# Sheet1.net
KiCad netlist of a schematic drawn in Altium Designer
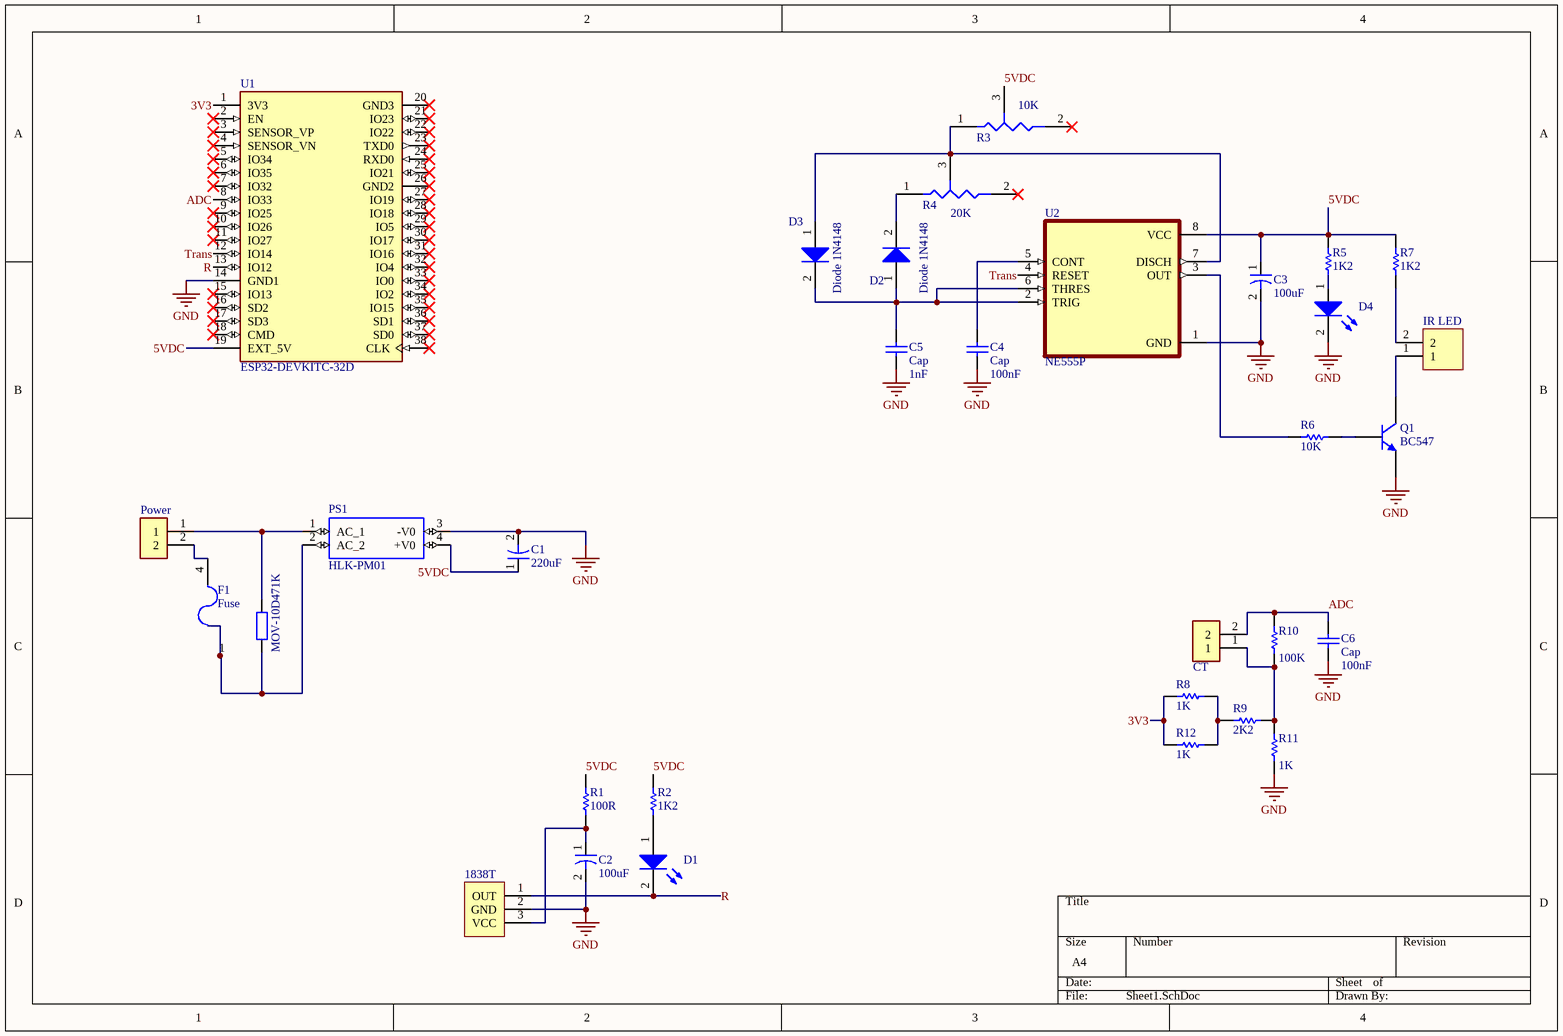
[diagram p0: Sheet1.SchDoc]

(export (version "E")
  (design (tool "Eeschema 10.0.6"))
  (components
    (comp (ref "1838T")
      (value "Header 3")
      (footprint "TSOP 1838T")
      (description "Header, 3-Pin")
      (fields (field (name "PUBLISHER") "Altium Limited"))
      (libsource (lib "Miscellaneous Connectors") (part "Header 3"))
    )
    (comp (ref "C1")
      (value "220uF")
      (footprint "CAPR5-4X5")
      (description "Capacitor")
      (fields (field (name "Comment") "Cap2") (field (name "PUBLISHER") "Altium Limited"))
      (libsource (lib "Miscellaneous Devices") (part "Cap2"))
    )
    (comp (ref "C2")
      (value "100uF")
      (footprint "CAPR5-4X5")
      (description "Capacitor")
      (fields (field (name "Comment") "Cap2") (field (name "PUBLISHER") "Altium Limited"))
      (libsource (lib "Miscellaneous Devices") (part "Cap2"))
    )
    (comp (ref "C3")
      (value "100uF")
      (footprint "CAPR5-4X5")
      (description "Capacitor")
      (fields (field (name "Comment") "Cap2") (field (name "PUBLISHER") "Altium Limited"))
      (libsource (lib "Miscellaneous Devices") (part "Cap2"))
    )
    (comp (ref "C4")
      (value "Cap")
      (footprint "RAD-0.3")
      (description "Capacitor")
      (fields (field (name "ALTIUM_VALUE") "100nF") (field (name "PUBLISHER") "Altium Limited"))
      (libsource (lib "Miscellaneous Devices") (part "Cap"))
    )
    (comp (ref "C5")
      (value "Cap")
      (footprint "RAD-0.3")
      (description "Capacitor")
      (fields (field (name "ALTIUM_VALUE") "1nF") (field (name "PUBLISHER") "Altium Limited"))
      (libsource (lib "Miscellaneous Devices") (part "Cap"))
    )
    (comp (ref "C6")
      (value "Cap")
      (footprint "RAD-0.3")
      (description "Capacitor")
      (fields (field (name "ALTIUM_VALUE") "100nF") (field (name "PUBLISHER") "Altium Limited"))
      (libsource (lib "Miscellaneous Devices") (part "Cap"))
    )
    (comp (ref "CT")
      (value "282837-2")
      (footprint "TE_282837-2")
      (description "Connector Terminal Blocks Receptacle 2 Position 5.08mm Solder Straight Thru-Hole 13.5A/Contact")
      (fields (field (name "MF") "TE Connectivity") (field (name "DIGI-KEY_PART_NUMBER") "A113320-ND"))
      (libsource (lib "282837-2") (part "282837-2"))
    )
    (comp (ref "D1")
      (value "LED")
      (footprint "LED")
      (description "Typical INFRARED GaAs LED")
      (fields (field (name "PUBLISHER") "Altium Limited"))
      (libsource (lib "Miscellaneous Devices") (part "LED0"))
    )
    (comp (ref "D2")
      (value "Diode 1N4148")
      (footprint "Diode")
      (description "High Conductance Fast Diode")
      (fields (field (name "PUBLISHER") "Altium Limited"))
      (libsource (lib "Miscellaneous Devices") (part "Diode 1N4448"))
    )
    (comp (ref "D3")
      (value "Diode 1N4148")
      (footprint "Diode")
      (description "High Conductance Fast Diode")
      (fields (field (name "PUBLISHER") "Altium Limited"))
      (libsource (lib "Miscellaneous Devices") (part "Diode 1N4448"))
    )
    (comp (ref "D4")
      (value "LED")
      (footprint "LED")
      (description "Typical INFRARED GaAs LED")
      (fields (field (name "PUBLISHER") "Altium Limited"))
      (libsource (lib "Miscellaneous Devices") (part "LED0"))
    )
    (comp (ref "F1")
      (value "Fuse")
      (footprint "Fuse Holder")
      (fields (field (name "PUBLISHER") "Altium Limited"))
      (libsource (lib "Miscellaneous Devices") (part "Fuse 2"))
    )
    (comp (ref "IR LED")
      (value "Header 2")
      (footprint "HDR1X2")
      (description "Header, 2-Pin")
      (fields (field (name "PUBLISHER") "Altium Limited"))
      (libsource (lib "Miscellaneous Connectors") (part "Header 2"))
    )
    (comp (ref "MOV-10D471K")
      (value "~")
      (footprint "AXIAL-0.4")
      (description "Resistor")
      (fields (field (name "PUBLISHER") "Altium Limited"))
      (libsource (lib "Miscellaneous Devices") (part "Res2"))
    )
    (comp (ref "Power")
      (value "282837-2")
      (footprint "TE_282837-2")
      (description "Connector Terminal Blocks Receptacle 2 Position 5.08mm Solder Straight Thru-Hole 13.5A/Contact")
      (fields (field (name "MF") "TE Connectivity") (field (name "DIGI-KEY_PART_NUMBER") "A113320-ND"))
      (libsource (lib "") (part "282837-2_1"))
    )
    (comp (ref "PS1")
      (value "HLK-PM01")
      (footprint "HLKPM01")
      (fields (field (name "MF") "Hi-link") (field (name "MP") "hlk-pm01"))
      (libsource (lib "HLK-PM01") (part "HLK-PM01"))
    )
    (comp (ref "Q1")
      (value "BC547")
      (footprint "TO-226-AA")
      (description "NPN Bipolar Transistor")
      (fields (field (name "PUBLISHER") "Altium Limited"))
      (libsource (lib "Miscellaneous Devices") (part "NPN"))
    )
    (comp (ref "R1")
      (value "100R")
      (footprint "AXIAL-0.3")
      (description "Resistor")
      (fields (field (name "Comment") "Res1") (field (name "PUBLISHER") "Altium Limited"))
      (libsource (lib "Miscellaneous Devices") (part "Res1"))
    )
    (comp (ref "R2")
      (value "1K2")
      (footprint "AXIAL-0.3")
      (description "Resistor")
      (fields (field (name "Comment") "Res1") (field (name "PUBLISHER") "Altium Limited"))
      (libsource (lib "Miscellaneous Devices") (part "Res1"))
    )
    (comp (ref "R3")
      (value "10K")
      (footprint "Bien tro tam giac")
      (description "Tapped Resistor")
      (fields (field (name "Comment") "Res Tap") (field (name "PUBLISHER") "Altium Limited"))
      (libsource (lib "Miscellaneous Devices") (part "Res Tap"))
    )
    (comp (ref "R4")
      (value "20K")
      (footprint "Bien tro tam giac")
      (description "Tapped Resistor")
      (fields (field (name "Comment") "Res Tap") (field (name "PUBLISHER") "Altium Limited"))
      (libsource (lib "Miscellaneous Devices") (part "Res Tap"))
    )
    (comp (ref "R5")
      (value "1K2")
      (footprint "AXIAL-0.3")
      (description "Resistor")
      (fields (field (name "Comment") "Res1") (field (name "PUBLISHER") "Altium Limited"))
      (libsource (lib "Miscellaneous Devices") (part "Res1"))
    )
    (comp (ref "R6")
      (value "10K")
      (footprint "AXIAL-0.3")
      (description "Resistor")
      (fields (field (name "Comment") "Res1") (field (name "PUBLISHER") "Altium Limited"))
      (libsource (lib "Miscellaneous Devices") (part "Res1"))
    )
    (comp (ref "R7")
      (value "1K2")
      (footprint "AXIAL-0.3")
      (description "Resistor")
      (fields (field (name "Comment") "Res1") (field (name "PUBLISHER") "Altium Limited"))
      (libsource (lib "Miscellaneous Devices") (part "Res1"))
    )
    (comp (ref "R8")
      (value "1K")
      (footprint "AXIAL-0.3")
      (description "Resistor")
      (fields (field (name "Comment") "Res1") (field (name "PUBLISHER") "Altium Limited"))
      (libsource (lib "Miscellaneous Devices") (part "Res1"))
    )
    (comp (ref "R9")
      (value "2K2")
      (footprint "AXIAL-0.3")
      (description "Resistor")
      (fields (field (name "Comment") "Res1") (field (name "PUBLISHER") "Altium Limited"))
      (libsource (lib "Miscellaneous Devices") (part "Res1"))
    )
    (comp (ref "R10")
      (value "100K")
      (footprint "AXIAL-0.3")
      (description "Resistor")
      (fields (field (name "Comment") "Res1") (field (name "PUBLISHER") "Altium Limited"))
      (libsource (lib "Miscellaneous Devices") (part "Res1"))
    )
    (comp (ref "R11")
      (value "1K")
      (footprint "AXIAL-0.3")
      (description "Resistor")
      (fields (field (name "Comment") "Res1") (field (name "PUBLISHER") "Altium Limited"))
      (libsource (lib "Miscellaneous Devices") (part "Res1"))
    )
    (comp (ref "R12")
      (value "1K")
      (footprint "AXIAL-0.3")
      (description "Resistor")
      (fields (field (name "Comment") "Res1") (field (name "PUBLISHER") "Altium Limited"))
      (libsource (lib "Miscellaneous Devices") (part "Res1"))
    )
    (comp (ref "U1")
      (value "ESP32-DEVKITC-32D")
      (footprint "MODULE_ESP32-DEVKITC-32D")
      (fields (field (name "MF") "Espressif Systems"))
      (libsource (lib "ESP32-DEVKITC-32D") (part "ESP32-DEVKITC-32D"))
    )
    (comp (ref "U2")
      (value "NE555P")
      (footprint "NE555 SOP")
      (description "Single Precision Timer")
      (fields (field (name "MF") "Texas Instruments"))
      (libsource (lib "NE555P") (part "NE555P"))
    )
  )
  (nets
    (net (code "1") (name "/3V3") (class "Default")
      (node (ref "R12") (pin "2") (pinfunction "2_2") (pintype "passive"))
      (node (ref "R8") (pin "2") (pinfunction "2_2") (pintype "passive"))
      (node (ref "U1") (pin "1") (pinfunction "3V3_1") (pintype "power_in"))
    )
    (net (code "2") (name "/5VDC") (class "Default")
      (node (ref "C1") (pin "1") (pinfunction "1_1") (pintype "passive"))
      (node (ref "C3") (pin "1") (pinfunction "1_1") (pintype "passive"))
      (node (ref "PS1") (pin "4") (pinfunction "+V0_4") (pintype "bidirectional"))
      (node (ref "R1") (pin "2") (pinfunction "2_2") (pintype "passive"))
      (node (ref "R2") (pin "2") (pinfunction "2_2") (pintype "passive"))
      (node (ref "R3") (pin "3") (pinfunction "TAP_3") (pintype "passive"))
      (node (ref "R5") (pin "1") (pinfunction "1_1") (pintype "passive"))
      (node (ref "R7") (pin "2") (pinfunction "2_2") (pintype "passive"))
      (node (ref "U1") (pin "19") (pinfunction "EXT_5V_19") (pintype "power_in"))
      (node (ref "U2") (pin "8") (pinfunction "VCC_8") (pintype "power_in"))
    )
    (net (code "3") (name "/ADC") (class "Default")
      (node (ref "C6") (pin "2") (pinfunction "2_2") (pintype "passive"))
      (node (ref "CT") (pin "2") (pinfunction "2_2") (pintype "passive"))
      (node (ref "R10") (pin "2") (pinfunction "2_2") (pintype "passive"))
      (node (ref "U1") (pin "8") (pinfunction "IO33_8") (pintype "bidirectional"))
    )
    (net (code "4") (name "/R") (class "Default")
      (node (ref "1838T") (pin "1") (pinfunction "OUT_1") (pintype "passive"))
      (node (ref "D1") (pin "2") (pinfunction "K_2") (pintype "passive"))
      (node (ref "U1") (pin "13") (pinfunction "IO12_13") (pintype "bidirectional"))
    )
    (net (code "5") (name "/Trans") (class "Default")
      (node (ref "U1") (pin "12") (pinfunction "IO14_12") (pintype "bidirectional"))
      (node (ref "U2") (pin "4") (pinfunction "RESET_4") (pintype "input"))
    )
    (net (code "6") (name "GND") (class "Default")
      (node (ref "1838T") (pin "2") (pinfunction "GND_2") (pintype "passive"))
      (node (ref "C1") (pin "2") (pinfunction "2_2") (pintype "passive"))
      (node (ref "C2") (pin "2") (pinfunction "2_2") (pintype "passive"))
      (node (ref "C3") (pin "2") (pinfunction "2_2") (pintype "passive"))
      (node (ref "C4") (pin "1") (pinfunction "1_1") (pintype "passive"))
      (node (ref "C5") (pin "1") (pinfunction "1_1") (pintype "passive"))
      (node (ref "C6") (pin "1") (pinfunction "1_1") (pintype "passive"))
      (node (ref "D4") (pin "2") (pinfunction "K_2") (pintype "passive"))
      (node (ref "PS1") (pin "3") (pinfunction "-V0_3") (pintype "bidirectional"))
      (node (ref "Q1") (pin "3") (pinfunction "E_3") (pintype "passive"))
      (node (ref "R11") (pin "1") (pinfunction "1_1") (pintype "passive"))
      (node (ref "U1") (pin "14") (pinfunction "GND1_14") (pintype "power_in"))
      (node (ref "U2") (pin "1") (pinfunction "GND_1") (pintype "power_in"))
    )
    (net (code "7") (name "Net-(1838T-VCC)") (class "Default")
      (node (ref "1838T") (pin "3") (pinfunction "VCC_3") (pintype "passive"))
      (node (ref "C2") (pin "1") (pinfunction "1_1") (pintype "passive"))
      (node (ref "R1") (pin "1") (pinfunction "1_1") (pintype "passive"))
    )
    (net (code "8") (name "Net-(CT-Pad1)") (class "Default")
      (node (ref "CT") (pin "1") (pinfunction "1_1") (pintype "passive"))
      (node (ref "R10") (pin "1") (pinfunction "1_1") (pintype "passive"))
      (node (ref "R11") (pin "2") (pinfunction "2_2") (pintype "passive"))
      (node (ref "R9") (pin "1") (pinfunction "1_1") (pintype "passive"))
    )
    (net (code "9") (name "Net-(D1-A)") (class "Default")
      (node (ref "D1") (pin "1") (pinfunction "A_1") (pintype "passive"))
      (node (ref "R2") (pin "1") (pinfunction "1_1") (pintype "passive"))
    )
    (net (code "10") (name "Net-(D2-A)") (class "Default")
      (node (ref "C5") (pin "2") (pinfunction "2_2") (pintype "passive"))
      (node (ref "D2") (pin "1") (pinfunction "A_1") (pintype "passive"))
      (node (ref "D3") (pin "2") (pinfunction "K_2") (pintype "passive"))
      (node (ref "U2") (pin "2") (pinfunction "TRIG_2") (pintype "input"))
      (node (ref "U2") (pin "6") (pinfunction "THRES_6") (pintype "input"))
    )
    (net (code "11") (name "Net-(D2-K)") (class "Default")
      (node (ref "D2") (pin "2") (pinfunction "K_2") (pintype "passive"))
      (node (ref "R4") (pin "1") (pinfunction "A_1") (pintype "passive"))
    )
    (net (code "12") (name "Net-(D3-A)") (class "Default")
      (node (ref "D3") (pin "1") (pinfunction "A_1") (pintype "passive"))
      (node (ref "R3") (pin "1") (pinfunction "A_1") (pintype "passive"))
      (node (ref "R4") (pin "3") (pinfunction "TAP_3") (pintype "passive"))
      (node (ref "U2") (pin "7") (pinfunction "DISCH_7") (pintype "output"))
    )
    (net (code "13") (name "Net-(D4-A)") (class "Default")
      (node (ref "D4") (pin "1") (pinfunction "A_1") (pintype "passive"))
      (node (ref "R5") (pin "2") (pinfunction "2_2") (pintype "passive"))
    )
    (net (code "14") (name "Net-(F1-Pad4)") (class "Default")
      (node (ref "F1") (pin "4") (pinfunction "4_4") (pintype "passive"))
      (node (ref "Power") (pin "2") (pinfunction "2_2") (pintype "passive"))
    )
    (net (code "15") (name "Net-(IR LED-Pad2)") (class "Default")
      (node (ref "IR LED") (pin "2") (pinfunction "2_2") (pintype "passive"))
      (node (ref "R7") (pin "1") (pinfunction "1_1") (pintype "passive"))
    )
    (net (code "16") (name "Net-(PS1-AC_1)") (class "Default")
      (node (ref "MOV-10D471K") (pin "2") (pinfunction "2_2") (pintype "passive"))
      (node (ref "PS1") (pin "1") (pinfunction "AC_1_1") (pintype "bidirectional"))
      (node (ref "Power") (pin "1") (pinfunction "1_1") (pintype "passive"))
    )
    (net (code "17") (name "Net-(PS1-AC_2)") (class "Default")
      (node (ref "F1") (pin "1") (pinfunction "1_1") (pintype "passive"))
      (node (ref "MOV-10D471K") (pin "1") (pinfunction "1_1") (pintype "passive"))
      (node (ref "PS1") (pin "2") (pinfunction "AC_2_2") (pintype "bidirectional"))
    )
    (net (code "18") (name "Net-(Q1-B)") (class "Default")
      (node (ref "Q1") (pin "2") (pinfunction "B_2") (pintype "passive"))
      (node (ref "R6") (pin "2") (pinfunction "2_2") (pintype "passive"))
    )
    (net (code "19") (name "Net-(Q1-C)") (class "Default")
      (node (ref "IR LED") (pin "1") (pinfunction "1_1") (pintype "passive"))
      (node (ref "Q1") (pin "1") (pinfunction "C_1") (pintype "passive"))
    )
    (net (code "20") (name "Net-(R12-Pad1)") (class "Default")
      (node (ref "R12") (pin "1") (pinfunction "1_1") (pintype "passive"))
      (node (ref "R8") (pin "1") (pinfunction "1_1") (pintype "passive"))
      (node (ref "R9") (pin "2") (pinfunction "2_2") (pintype "passive"))
    )
    (net (code "21") (name "Net-(U2-CONT)") (class "Default")
      (node (ref "C4") (pin "2") (pinfunction "2_2") (pintype "passive"))
      (node (ref "U2") (pin "5") (pinfunction "CONT_5") (pintype "input"))
    )
    (net (code "22") (name "Net-(U2-OUT)") (class "Default")
      (node (ref "R6") (pin "1") (pinfunction "1_1") (pintype "passive"))
      (node (ref "U2") (pin "3") (pinfunction "OUT_3") (pintype "output"))
    )
    (net (code "23") (name "unconnected-(R3-B-Pad2)") (class "Default")
      (node (ref "R3") (pin "2") (pinfunction "B_2") (pintype "passive+no_connect"))
    )
    (net (code "24") (name "unconnected-(R4-B-Pad2)") (class "Default")
      (node (ref "R4") (pin "2") (pinfunction "B_2") (pintype "passive+no_connect"))
    )
    (net (code "25") (name "unconnected-(U1-CLK-Pad38)") (class "Default")
      (node (ref "U1") (pin "38") (pinfunction "CLK_38") (pintype "input+no_connect"))
    )
    (net (code "26") (name "unconnected-(U1-CMD-Pad18)") (class "Default")
      (node (ref "U1") (pin "18") (pinfunction "CMD_18") (pintype "bidirectional+no_connect"))
    )
    (net (code "27") (name "unconnected-(U1-EN-Pad2)") (class "Default")
      (node (ref "U1") (pin "2") (pinfunction "EN_2") (pintype "input+no_connect"))
    )
    (net (code "28") (name "unconnected-(U1-GND2-Pad26)") (class "Default")
      (node (ref "U1") (pin "26") (pinfunction "GND2_26") (pintype "power_in+no_connect"))
    )
    (net (code "29") (name "unconnected-(U1-GND3-Pad20)") (class "Default")
      (node (ref "U1") (pin "20") (pinfunction "GND3_20") (pintype "power_in+no_connect"))
    )
    (net (code "30") (name "unconnected-(U1-IO0-Pad33)") (class "Default")
      (node (ref "U1") (pin "33") (pinfunction "IO0_33") (pintype "bidirectional+no_connect"))
    )
    (net (code "31") (name "unconnected-(U1-IO2-Pad34)") (class "Default")
      (node (ref "U1") (pin "34") (pinfunction "IO2_34") (pintype "bidirectional+no_connect"))
    )
    (net (code "32") (name "unconnected-(U1-IO4-Pad32)") (class "Default")
      (node (ref "U1") (pin "32") (pinfunction "IO4_32") (pintype "bidirectional+no_connect"))
    )
    (net (code "33") (name "unconnected-(U1-IO5-Pad29)") (class "Default")
      (node (ref "U1") (pin "29") (pinfunction "IO5_29") (pintype "bidirectional+no_connect"))
    )
    (net (code "34") (name "unconnected-(U1-IO13-Pad15)") (class "Default")
      (node (ref "U1") (pin "15") (pinfunction "IO13_15") (pintype "bidirectional+no_connect"))
    )
    (net (code "35") (name "unconnected-(U1-IO15-Pad35)") (class "Default")
      (node (ref "U1") (pin "35") (pinfunction "IO15_35") (pintype "bidirectional+no_connect"))
    )
    (net (code "36") (name "unconnected-(U1-IO16-Pad31)") (class "Default")
      (node (ref "U1") (pin "31") (pinfunction "IO16_31") (pintype "bidirectional+no_connect"))
    )
    (net (code "37") (name "unconnected-(U1-IO17-Pad30)") (class "Default")
      (node (ref "U1") (pin "30") (pinfunction "IO17_30") (pintype "bidirectional+no_connect"))
    )
    (net (code "38") (name "unconnected-(U1-IO18-Pad28)") (class "Default")
      (node (ref "U1") (pin "28") (pinfunction "IO18_28") (pintype "bidirectional+no_connect"))
    )
    (net (code "39") (name "unconnected-(U1-IO19-Pad27)") (class "Default")
      (node (ref "U1") (pin "27") (pinfunction "IO19_27") (pintype "bidirectional+no_connect"))
    )
    (net (code "40") (name "unconnected-(U1-IO21-Pad25)") (class "Default")
      (node (ref "U1") (pin "25") (pinfunction "IO21_25") (pintype "bidirectional+no_connect"))
    )
    (net (code "41") (name "unconnected-(U1-IO22-Pad22)") (class "Default")
      (node (ref "U1") (pin "22") (pinfunction "IO22_22") (pintype "bidirectional+no_connect"))
    )
    (net (code "42") (name "unconnected-(U1-IO23-Pad21)") (class "Default")
      (node (ref "U1") (pin "21") (pinfunction "IO23_21") (pintype "bidirectional+no_connect"))
    )
    (net (code "43") (name "unconnected-(U1-IO25-Pad9)") (class "Default")
      (node (ref "U1") (pin "9") (pinfunction "IO25_9") (pintype "bidirectional+no_connect"))
    )
    (net (code "44") (name "unconnected-(U1-IO26-Pad10)") (class "Default")
      (node (ref "U1") (pin "10") (pinfunction "IO26_10") (pintype "bidirectional+no_connect"))
    )
    (net (code "45") (name "unconnected-(U1-IO27-Pad11)") (class "Default")
      (node (ref "U1") (pin "11") (pinfunction "IO27_11") (pintype "bidirectional+no_connect"))
    )
    (net (code "46") (name "unconnected-(U1-IO32-Pad7)") (class "Default")
      (node (ref "U1") (pin "7") (pinfunction "IO32_7") (pintype "bidirectional+no_connect"))
    )
    (net (code "47") (name "unconnected-(U1-IO34-Pad5)") (class "Default")
      (node (ref "U1") (pin "5") (pinfunction "IO34_5") (pintype "bidirectional+no_connect"))
    )
    (net (code "48") (name "unconnected-(U1-IO35-Pad6)") (class "Default")
      (node (ref "U1") (pin "6") (pinfunction "IO35_6") (pintype "bidirectional+no_connect"))
    )
    (net (code "49") (name "unconnected-(U1-RXD0-Pad24)") (class "Default")
      (node (ref "U1") (pin "24") (pinfunction "RXD0_24") (pintype "input+no_connect"))
    )
    (net (code "50") (name "unconnected-(U1-SD0-Pad37)") (class "Default")
      (node (ref "U1") (pin "37") (pinfunction "SD0_37") (pintype "bidirectional+no_connect"))
    )
    (net (code "51") (name "unconnected-(U1-SD1-Pad36)") (class "Default")
      (node (ref "U1") (pin "36") (pinfunction "SD1_36") (pintype "bidirectional+no_connect"))
    )
    (net (code "52") (name "unconnected-(U1-SD2-Pad16)") (class "Default")
      (node (ref "U1") (pin "16") (pinfunction "SD2_16") (pintype "bidirectional+no_connect"))
    )
    (net (code "53") (name "unconnected-(U1-SD3-Pad17)") (class "Default")
      (node (ref "U1") (pin "17") (pinfunction "SD3_17") (pintype "bidirectional+no_connect"))
    )
    (net (code "54") (name "unconnected-(U1-SENSOR_VN-Pad4)") (class "Default")
      (node (ref "U1") (pin "4") (pinfunction "SENSOR_VN_4") (pintype "input+no_connect"))
    )
    (net (code "55") (name "unconnected-(U1-SENSOR_VP-Pad3)") (class "Default")
      (node (ref "U1") (pin "3") (pinfunction "SENSOR_VP_3") (pintype "input+no_connect"))
    )
    (net (code "56") (name "unconnected-(U1-TXD0-Pad23)") (class "Default")
      (node (ref "U1") (pin "23") (pinfunction "TXD0_23") (pintype "output+no_connect"))
    )
  )
)
